# Soprano2GX-015.net
KiCad netlist of a schematic drawn in EAGLE
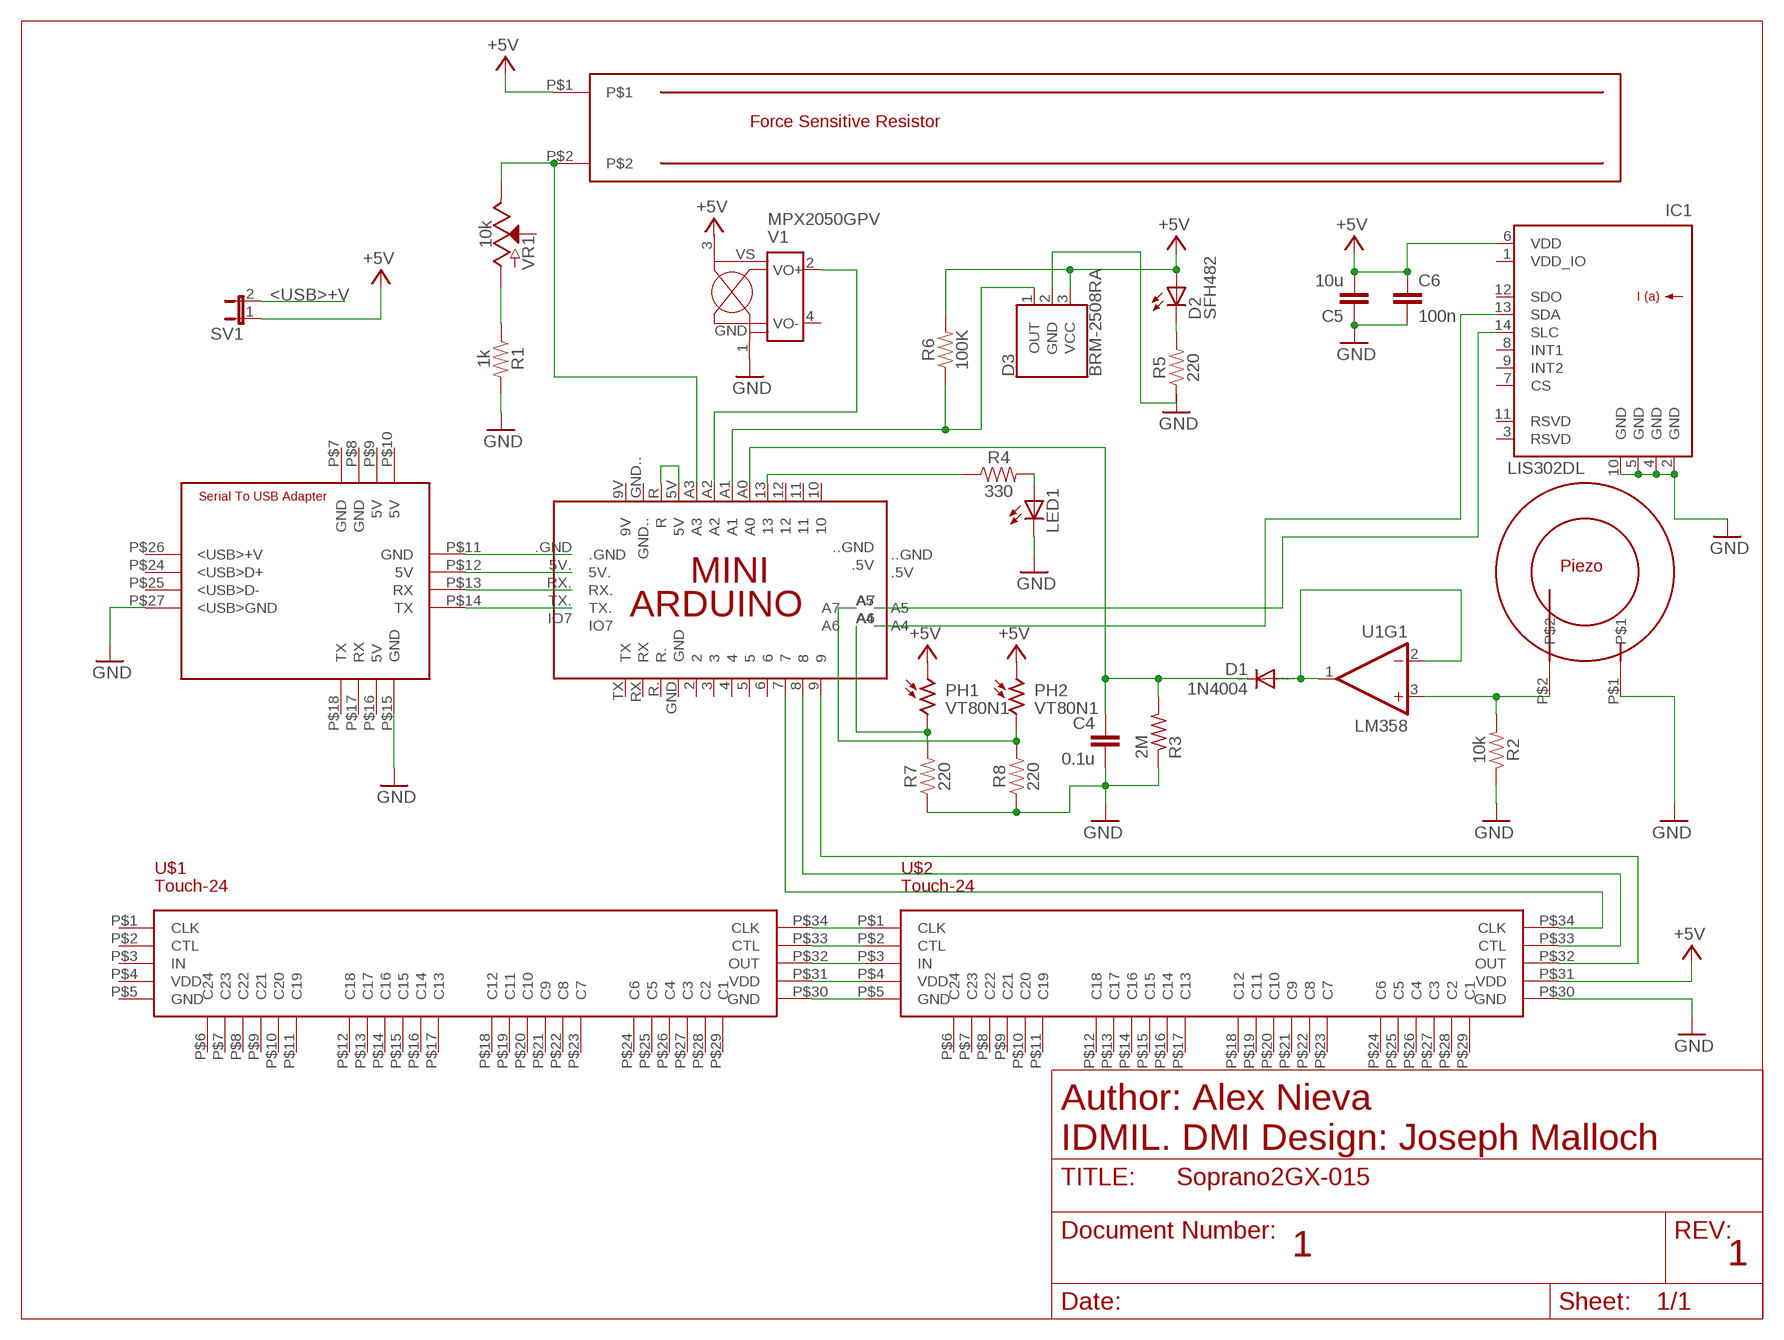
[diagram p0: schematic, sheet 1]

(export (version "E")
  (design (tool "Eeschema 10.0.6"))
  (components
    (comp (ref "C4")
      (value "0.1u")
      (footprint "eagle-import:C5B5.5")
      (libsource (lib "eagle-import") (part "C5/5.5"))
    )
    (comp (ref "C5")
      (value "10u")
      (footprint "eagle-import:C5B5.5")
      (libsource (lib "eagle-import") (part "C5/5.5"))
    )
    (comp (ref "C6")
      (value "100n")
      (footprint "eagle-import:C5B5.5")
      (libsource (lib "eagle-import") (part "C5/5.5"))
    )
    (comp (ref "D1")
      (value "1N4004")
      (footprint "eagle-import:DO41-10")
      (libsource (lib "eagle-import") (part "1N4004"))
    )
    (comp (ref "D2")
      (value "SFH482")
      (footprint "eagle-import:SFH482")
      (libsource (lib "eagle-import") (part "SFH482"))
    )
    (comp (ref "D3")
      (value "BRM-2508RA")
      (footprint "eagle-import:BRM-2508")
      (libsource (lib "eagle-import") (part "BRM-2508RA"))
    )
    (comp (ref "IC1")
      (value "LIS302DL")
      (footprint "eagle-import:LGA-14")
      (libsource (lib "eagle-import") (part "LIS302DL"))
    )
    (comp (ref "LED1")
      (value "LED3MM")
      (footprint "eagle-import:LED3MM")
      (libsource (lib "eagle-import") (part "LED3MM"))
    )
    (comp (ref "PCB1")
      (value "ARDUINO_MINI")
      (footprint "eagle-import:ARDUINO_MINI")
      (libsource (lib "eagle-import") (part "ARDUINO_MINI"))
    )
    (comp (ref "PH1")
      (value "VT80N1")
      (footprint "eagle-import:VT800")
      (libsource (lib "eagle-import") (part "VT80N1"))
    )
    (comp (ref "PH2")
      (value "VT80N1")
      (footprint "eagle-import:VT800")
      (libsource (lib "eagle-import") (part "VT80N1"))
    )
    (comp (ref "R1")
      (value "1k")
      (footprint "eagle-import:AXIAL-0.3")
      (libsource (lib "eagle-import") (part "1KOHM-HORIZ-1/4W-1%"))
    )
    (comp (ref "R2")
      (value "10k")
      (footprint "eagle-import:AXIAL-0.3")
      (libsource (lib "eagle-import") (part "10KOHM-HORIZ-1/4W-1%"))
    )
    (comp (ref "R3")
      (value "2M")
      (footprint "eagle-import:0204_7")
      (libsource (lib "eagle-import") (part "R-US_0204/7"))
    )
    (comp (ref "R4")
      (value "330")
      (footprint "eagle-import:AXIAL-0.3")
      (libsource (lib "eagle-import") (part "1KOHM-HORIZ-1/4W-1%"))
    )
    (comp (ref "R5")
      (value "220")
      (footprint "eagle-import:AXIAL-0.3")
      (libsource (lib "eagle-import") (part "1KOHM-HORIZ-1/4W-1%"))
    )
    (comp (ref "R6")
      (value "100K")
      (footprint "eagle-import:AXIAL-0.3")
      (libsource (lib "eagle-import") (part "1KOHM-HORIZ-1/4W-1%"))
    )
    (comp (ref "R7")
      (value "220")
      (footprint "eagle-import:AXIAL-0.3")
      (libsource (lib "eagle-import") (part "1KOHM-HORIZ-1/4W-1%"))
    )
    (comp (ref "R8")
      (value "220")
      (footprint "eagle-import:AXIAL-0.3")
      (libsource (lib "eagle-import") (part "1KOHM-HORIZ-1/4W-1%"))
    )
    (comp (ref "SV1")
      (value "JP1E")
      (footprint "eagle-import:JP1")
      (libsource (lib "eagle-import") (part "JP1E"))
    )
    (comp (ref "U$1")
      (value "TOUCH-24TOUCH-24")
      (footprint "eagle-import:TOUCH24")
      (libsource (lib "eagle-import") (part "TOUCH-24TOUCH-24"))
    )
    (comp (ref "U$2")
      (value "TOUCH-24TOUCH-24")
      (footprint "eagle-import:TOUCH24")
      (libsource (lib "eagle-import") (part "TOUCH-24TOUCH-24"))
    )
    (comp (ref "U$4")
      (value "SERIAL_TO_USB_ARDUINO_MINI")
      (footprint "eagle-import:SERIAL_TO_USB_ARDUINO")
      (libsource (lib "eagle-import") (part "SERIAL_TO_USB_ARDUINO_MINI"))
    )
    (comp (ref "U$5")
      (value "FSR_T-STICK")
      (footprint "eagle-import:FSR_T-STICK")
      (libsource (lib "eagle-import") (part "FSR_T-STICK"))
    )
    (comp (ref "U$6")
      (value "PIEZO_TSTICK")
      (footprint "eagle-import:PIEZO_TSTICK")
      (libsource (lib "eagle-import") (part "PIEZO_TSTICK"))
    )
    (comp (ref "U1")
      (value "LM358")
      (footprint "eagle-import:DIP08")
      (libsource (lib "eagle-import") (part "LM358"))
    )
    (comp (ref "V1")
      (value "MPX2050GPV")
      (footprint "eagle-import:MPX2050GPV")
      (fields (field (name "MF") "MOTOROLA") (field (name "MPN") "MPX2050GP"))
      (libsource (lib "eagle-import") (part "MPX2050GPV"))
    )
    (comp (ref "VR1")
      (value "10k")
      (footprint "eagle-import:POT-PTH-ALPS")
      (libsource (lib "eagle-import") (part "POTENTIOMETER-PTH-9MM-1/20W-20%"))
    )
  )
  (nets
    (net (code "1") (name "+5V") (class "Default")
      (node (ref "C5") (pin "2") (pinfunction "2_2") (pintype "passive"))
      (node (ref "C6") (pin "1") (pinfunction "1_1") (pintype "passive"))
      (node (ref "D2") (pin "A") (pinfunction "A_A") (pintype "passive"))
      (node (ref "D3") (pin "3") (pinfunction "VCC_3") (pintype "bidirectional"))
      (node (ref "IC1") (pin "6") (pinfunction "VDD_6") (pintype "power_in"))
      (node (ref "PCB1") (pin "5V.") (pinfunction "5V._5V.") (pintype "bidirectional"))
      (node (ref "R6") (pin "P$2") (pinfunction "2_P$2") (pintype "passive"))
      (node (ref "SV1") (pin "1") (pinfunction "1_1") (pintype "passive"))
      (node (ref "U$2") (pin "P$31") (pinfunction "VDD_P$31") (pintype "bidirectional"))
      (node (ref "U$4") (pin "P$12") (pinfunction "5V_P$12") (pintype "bidirectional"))
      (node (ref "U$5") (pin "P$1") (pinfunction "P$1_P$1") (pintype "bidirectional"))
    )
    (net (code "2") (name "/<USB>+V") (class "Default")
      (node (ref "SV1") (pin "2") (pinfunction "2_2") (pintype "passive"))
    )
    (net (code "3") (name "/VDD_IO") (class "Default")
      (node (ref "IC1") (pin "1") (pinfunction "VDD_IO_1") (pintype "power_in"))
    )
    (net (code "4") (name "GND") (class "Default")
      (node (ref "C4") (pin "2") (pinfunction "2_2") (pintype "passive"))
      (node (ref "C5") (pin "1") (pinfunction "1_1") (pintype "passive"))
      (node (ref "C6") (pin "2") (pinfunction "2_2") (pintype "passive"))
      (node (ref "IC1") (pin "10") (pinfunction "GND_10") (pintype "passive"))
      (node (ref "IC1") (pin "2") (pinfunction "GND_2") (pintype "power_in"))
      (node (ref "IC1") (pin "4") (pinfunction "GND_4") (pintype "passive"))
      (node (ref "IC1") (pin "5") (pinfunction "GND_5") (pintype "passive"))
      (node (ref "LED1") (pin "K") (pinfunction "C_K") (pintype "passive"))
      (node (ref "R1") (pin "P$2") (pinfunction "2_P$2") (pintype "passive"))
      (node (ref "R2") (pin "P$1") (pinfunction "1_P$1") (pintype "passive"))
      (node (ref "R3") (pin "1") (pinfunction "1_1") (pintype "passive"))
      (node (ref "R7") (pin "P$1") (pinfunction "1_P$1") (pintype "passive"))
      (node (ref "R8") (pin "P$1") (pinfunction "1_P$1") (pintype "passive"))
      (node (ref "U$2") (pin "P$30") (pinfunction "GND_P$30") (pintype "bidirectional"))
      (node (ref "U$4") (pin "P$15") (pinfunction "GND_P$15") (pintype "bidirectional"))
      (node (ref "U$4") (pin "P$27") (pinfunction "<USB>GND_P$27") (pintype "bidirectional"))
      (node (ref "U$6") (pin "P$1") (pinfunction "P$1_P$1") (pintype "bidirectional"))
      (node (ref "V1") (pin "1") (pinfunction "GND_1") (pintype "passive"))
    )
    (net (code "5") (name "Net-(C4-Pad1)") (class "Default")
      (node (ref "C4") (pin "1") (pinfunction "1_1") (pintype "passive"))
      (node (ref "D1") (pin "C") (pinfunction "C_C") (pintype "passive"))
      (node (ref "PCB1") (pin "A0") (pinfunction "A0_A0") (pintype "bidirectional"))
      (node (ref "R3") (pin "2") (pinfunction "2_2") (pintype "passive"))
    )
    (net (code "6") (name "Net-(D2-C)") (class "Default")
      (node (ref "D2") (pin "K") (pinfunction "C_K") (pintype "passive"))
      (node (ref "R5") (pin "P$2") (pinfunction "2_P$2") (pintype "passive"))
    )
    (net (code "7") (name "Net-(D3-GND)") (class "Default")
      (node (ref "D3") (pin "2") (pinfunction "GND_2") (pintype "bidirectional"))
      (node (ref "R5") (pin "P$1") (pinfunction "1_P$1") (pintype "passive"))
    )
    (net (code "8") (name "Net-(D3-OUT)") (class "Default")
      (node (ref "D3") (pin "1") (pinfunction "OUT_1") (pintype "bidirectional"))
      (node (ref "PCB1") (pin "A1") (pinfunction "A1_A1") (pintype "bidirectional"))
      (node (ref "R6") (pin "P$1") (pinfunction "1_P$1") (pintype "passive"))
    )
    (net (code "9") (name "Net-(IC1-SDA)") (class "Default")
      (node (ref "IC1") (pin "13") (pinfunction "SDA_13") (pintype "bidirectional"))
      (node (ref "PCB1") (pin "A4") (pinfunction "A4_A4") (pintype "bidirectional"))
    )
    (net (code "10") (name "Net-(IC1-SLC)") (class "Default")
      (node (ref "IC1") (pin "14") (pinfunction "SLC_14") (pintype "bidirectional"))
      (node (ref "PCB1") (pin "A5") (pinfunction "A5_A5") (pintype "bidirectional"))
    )
    (net (code "11") (name "Net-(PCB1-Pad.GND)") (class "Default")
      (node (ref "PCB1") (pin ".GND") (pinfunction ".GND_.GND") (pintype "bidirectional"))
      (node (ref "U$4") (pin "P$11") (pinfunction "GND_P$11") (pintype "bidirectional"))
    )
    (net (code "12") (name "Net-(PCB1-Pad5V)") (class "Default")
      (node (ref "PCB1") (pin "5V") (pinfunction "5V_5V") (pintype "bidirectional"))
      (node (ref "PCB1") (pin "R") (pinfunction "R_R") (pintype "bidirectional"))
    )
    (net (code "13") (name "Net-(PCB1-Pad7)") (class "Default")
      (node (ref "PCB1") (pin "7") (pinfunction "7_7") (pintype "bidirectional"))
      (node (ref "U$2") (pin "P$34") (pinfunction "CLK_P$34") (pintype "bidirectional"))
    )
    (net (code "14") (name "Net-(PCB1-Pad8)") (class "Default")
      (node (ref "PCB1") (pin "8") (pinfunction "8_8") (pintype "bidirectional"))
      (node (ref "U$2") (pin "P$33") (pinfunction "CTL_P$33") (pintype "bidirectional"))
    )
    (net (code "15") (name "Net-(PCB1-PadRX.)") (class "Default")
      (node (ref "PCB1") (pin "RX.") (pinfunction "RX._RX.") (pintype "bidirectional"))
      (node (ref "U$4") (pin "P$13") (pinfunction "RX_P$13") (pintype "bidirectional"))
    )
    (net (code "16") (name "Net-(PCB1-PadTX.)") (class "Default")
      (node (ref "PCB1") (pin "TX.") (pinfunction "TX._TX.") (pintype "bidirectional"))
      (node (ref "U$4") (pin "P$14") (pinfunction "TX_P$14") (pintype "bidirectional"))
    )
    (net (code "17") (name "Net-(R1-1)") (class "Default")
      (node (ref "R1") (pin "P$1") (pinfunction "1_P$1") (pintype "passive"))
      (node (ref "VR1") (pin "P$3") (pinfunction "A_P$3") (pintype "passive"))
    )
    (net (code "18") (name "Net-(R2-2)") (class "Default")
      (node (ref "R2") (pin "P$2") (pinfunction "2_P$2") (pintype "passive"))
      (node (ref "U$6") (pin "P$2") (pinfunction "P$2_P$2") (pintype "bidirectional"))
      (node (ref "U1") (pin "3") (pinfunction "+IN_3") (pintype "input"))
    )
    (net (code "19") (name "Net-(R4-1)") (class "Default")
      (node (ref "PCB1") (pin "13") (pinfunction "13_13") (pintype "bidirectional"))
      (node (ref "R4") (pin "P$1") (pinfunction "1_P$1") (pintype "passive"))
    )
    (net (code "20") (name "Net-(R4-2)") (class "Default")
      (node (ref "LED1") (pin "A") (pinfunction "A_A") (pintype "passive"))
      (node (ref "R4") (pin "P$2") (pinfunction "2_P$2") (pintype "passive"))
    )
    (net (code "21") (name "Net-(R7-2)") (class "Default")
      (node (ref "PCB1") (pin "A6") (pinfunction "A6_A6") (pintype "bidirectional"))
      (node (ref "PH1") (pin "2") (pinfunction "2_2") (pintype "passive"))
      (node (ref "R7") (pin "P$2") (pinfunction "2_P$2") (pintype "passive"))
    )
    (net (code "22") (name "Net-(R8-2)") (class "Default")
      (node (ref "PCB1") (pin "A7") (pinfunction "A7_A7") (pintype "bidirectional"))
      (node (ref "PH2") (pin "2") (pinfunction "2_2") (pintype "passive"))
      (node (ref "R8") (pin "P$2") (pinfunction "2_P$2") (pintype "passive"))
    )
    (net (code "23") (name "Net-(U$1-CLK-PadP$34)") (class "Default")
      (node (ref "U$1") (pin "P$34") (pinfunction "CLK_P$34") (pintype "bidirectional"))
      (node (ref "U$2") (pin "P$1") (pinfunction "CLK_P$1") (pintype "bidirectional"))
    )
    (net (code "24") (name "Net-(U$1-CTL-PadP$33)") (class "Default")
      (node (ref "U$1") (pin "P$33") (pinfunction "CTL_P$33") (pintype "bidirectional"))
      (node (ref "U$2") (pin "P$2") (pinfunction "CTL_P$2") (pintype "bidirectional"))
    )
    (net (code "25") (name "Net-(U$1-GND-PadP$30)") (class "Default")
      (node (ref "U$1") (pin "P$30") (pinfunction "GND_P$30") (pintype "bidirectional"))
      (node (ref "U$2") (pin "P$5") (pinfunction "GND_P$5") (pintype "bidirectional"))
    )
    (net (code "26") (name "Net-(U$1-OUT)") (class "Default")
      (node (ref "U$1") (pin "P$32") (pinfunction "OUT_P$32") (pintype "bidirectional"))
      (node (ref "U$2") (pin "P$3") (pinfunction "IN_P$3") (pintype "bidirectional"))
    )
    (net (code "27") (name "Net-(U$1-VDD-PadP$31)") (class "Default")
      (node (ref "U$1") (pin "P$31") (pinfunction "VDD_P$31") (pintype "bidirectional"))
      (node (ref "U$2") (pin "P$4") (pinfunction "VDD_P$4") (pintype "bidirectional"))
    )
    (net (code "28") (name "Net-(U$2-OUT)") (class "Default")
      (node (ref "PCB1") (pin "9") (pinfunction "9_9") (pintype "bidirectional"))
      (node (ref "U$2") (pin "P$32") (pinfunction "OUT_P$32") (pintype "bidirectional"))
    )
    (net (code "29") (name "Net-(U1A--IN)") (class "Default")
      (node (ref "D1") (pin "A") (pinfunction "A_A") (pintype "passive"))
      (node (ref "U1") (pin "1") (pinfunction "OUT_1") (pintype "output"))
      (node (ref "U1") (pin "2") (pinfunction "-IN_2") (pintype "input"))
    )
    (net (code "30") (name "Net-(V1-VO+)") (class "Default")
      (node (ref "PCB1") (pin "A2") (pinfunction "A2_A2") (pintype "bidirectional"))
      (node (ref "V1") (pin "2") (pinfunction "VO+_2") (pintype "passive"))
    )
    (net (code "31") (name "Net-(VR1-E)") (class "Default")
      (node (ref "PCB1") (pin "A3") (pinfunction "A3_A3") (pintype "bidirectional"))
      (node (ref "U$5") (pin "P$2") (pinfunction "P$2_P$2") (pintype "bidirectional"))
      (node (ref "VR1") (pin "P$1") (pinfunction "E_P$1") (pintype "passive"))
    )
    (net (code "32") (name "unconnected-(IC1-CS-Pad7)") (class "Default")
      (node (ref "IC1") (pin "7") (pinfunction "CS_7") (pintype "bidirectional"))
    )
    (net (code "33") (name "unconnected-(IC1-INT1-Pad8)") (class "Default")
      (node (ref "IC1") (pin "8") (pinfunction "INT1_8") (pintype "bidirectional"))
    )
    (net (code "34") (name "unconnected-(IC1-INT2-Pad9)") (class "Default")
      (node (ref "IC1") (pin "9") (pinfunction "INT2_9") (pintype "bidirectional"))
    )
    (net (code "35") (name "unconnected-(IC1-RSVD-Pad3)") (class "Default")
      (node (ref "IC1") (pin "3") (pinfunction "RSVD_3") (pintype "passive"))
    )
    (net (code "36") (name "unconnected-(IC1-RSVD-Pad11)") (class "Default")
      (node (ref "IC1") (pin "11") (pinfunction "RSVD_11") (pintype "passive"))
    )
    (net (code "37") (name "unconnected-(IC1-SDO-Pad12)") (class "Default")
      (node (ref "IC1") (pin "12") (pinfunction "SDO_12") (pintype "bidirectional"))
    )
    (net (code "38") (name "unconnected-(PCB1-Pad..GND)") (class "Default")
      (node (ref "PCB1") (pin "..GND") (pinfunction "..GND_..GND") (pintype "bidirectional"))
    )
    (net (code "39") (name "unconnected-(PCB1-Pad.5V)") (class "Default")
      (node (ref "PCB1") (pin ".5V") (pinfunction ".5V_.5V") (pintype "bidirectional"))
    )
    (net (code "40") (name "unconnected-(PCB1-Pad2)") (class "Default")
      (node (ref "PCB1") (pin "2") (pinfunction "2_2") (pintype "bidirectional"))
    )
    (net (code "41") (name "unconnected-(PCB1-Pad3)") (class "Default")
      (node (ref "PCB1") (pin "3") (pinfunction "3_3") (pintype "bidirectional"))
    )
    (net (code "42") (name "unconnected-(PCB1-Pad4)") (class "Default")
      (node (ref "PCB1") (pin "4") (pinfunction "4_4") (pintype "bidirectional"))
    )
    (net (code "43") (name "unconnected-(PCB1-Pad5)") (class "Default")
      (node (ref "PCB1") (pin "5") (pinfunction "5_5") (pintype "bidirectional"))
    )
    (net (code "44") (name "unconnected-(PCB1-Pad6)") (class "Default")
      (node (ref "PCB1") (pin "6") (pinfunction "6_6") (pintype "bidirectional"))
    )
    (net (code "45") (name "unconnected-(PCB1-Pad9V)") (class "Default")
      (node (ref "PCB1") (pin "9V") (pinfunction "9V_9V") (pintype "bidirectional"))
    )
    (net (code "46") (name "unconnected-(PCB1-Pad10)") (class "Default")
      (node (ref "PCB1") (pin "10") (pinfunction "10_10") (pintype "bidirectional"))
    )
    (net (code "47") (name "unconnected-(PCB1-Pad11)") (class "Default")
      (node (ref "PCB1") (pin "11") (pinfunction "11_11") (pintype "bidirectional"))
    )
    (net (code "48") (name "unconnected-(PCB1-Pad12)") (class "Default")
      (node (ref "PCB1") (pin "12") (pinfunction "12_12") (pintype "bidirectional"))
    )
    (net (code "49") (name "unconnected-(PCB1-PadGND)") (class "Default")
      (node (ref "PCB1") (pin "GND") (pinfunction "GND_GND") (pintype "bidirectional"))
    )
    (net (code "50") (name "unconnected-(PCB1-PadGND..)") (class "Default")
      (node (ref "PCB1") (pin "GND..") (pinfunction "GND.._GND..") (pintype "bidirectional"))
    )
    (net (code "51") (name "unconnected-(PCB1-PadIO7)") (class "Default")
      (node (ref "PCB1") (pin "IO7") (pinfunction "IO7_IO7") (pintype "bidirectional"))
    )
    (net (code "52") (name "unconnected-(PCB1-PadR.)") (class "Default")
      (node (ref "PCB1") (pin "R.") (pinfunction "R._R.") (pintype "bidirectional"))
    )
    (net (code "53") (name "unconnected-(PCB1-PadRX)") (class "Default")
      (node (ref "PCB1") (pin "RX") (pinfunction "RX_RX") (pintype "bidirectional"))
    )
    (net (code "54") (name "unconnected-(PCB1-PadTX)") (class "Default")
      (node (ref "PCB1") (pin "TX") (pinfunction "TX_TX") (pintype "bidirectional"))
    )
    (net (code "55") (name "unconnected-(PH1-Pad1)") (class "Default")
      (node (ref "PH1") (pin "1") (pinfunction "1_1") (pintype "passive"))
    )
    (net (code "56") (name "unconnected-(PH2-Pad1)") (class "Default")
      (node (ref "PH2") (pin "1") (pinfunction "1_1") (pintype "passive"))
    )
    (net (code "57") (name "unconnected-(U$1-C1-PadP$29)") (class "Default")
      (node (ref "U$1") (pin "P$29") (pinfunction "C1_P$29") (pintype "bidirectional"))
    )
    (net (code "58") (name "unconnected-(U$1-C2-PadP$28)") (class "Default")
      (node (ref "U$1") (pin "P$28") (pinfunction "C2_P$28") (pintype "bidirectional"))
    )
    (net (code "59") (name "unconnected-(U$1-C3-PadP$27)") (class "Default")
      (node (ref "U$1") (pin "P$27") (pinfunction "C3_P$27") (pintype "bidirectional"))
    )
    (net (code "60") (name "unconnected-(U$1-C4-PadP$26)") (class "Default")
      (node (ref "U$1") (pin "P$26") (pinfunction "C4_P$26") (pintype "bidirectional"))
    )
    (net (code "61") (name "unconnected-(U$1-C5-PadP$25)") (class "Default")
      (node (ref "U$1") (pin "P$25") (pinfunction "C5_P$25") (pintype "bidirectional"))
    )
    (net (code "62") (name "unconnected-(U$1-C6-PadP$24)") (class "Default")
      (node (ref "U$1") (pin "P$24") (pinfunction "C6_P$24") (pintype "bidirectional"))
    )
    (net (code "63") (name "unconnected-(U$1-C7-PadP$23)") (class "Default")
      (node (ref "U$1") (pin "P$23") (pinfunction "C7_P$23") (pintype "bidirectional"))
    )
    (net (code "64") (name "unconnected-(U$1-C8-PadP$22)") (class "Default")
      (node (ref "U$1") (pin "P$22") (pinfunction "C8_P$22") (pintype "bidirectional"))
    )
    (net (code "65") (name "unconnected-(U$1-C9-PadP$21)") (class "Default")
      (node (ref "U$1") (pin "P$21") (pinfunction "C9_P$21") (pintype "bidirectional"))
    )
    (net (code "66") (name "unconnected-(U$1-C10-PadP$20)") (class "Default")
      (node (ref "U$1") (pin "P$20") (pinfunction "C10_P$20") (pintype "bidirectional"))
    )
    (net (code "67") (name "unconnected-(U$1-C11-PadP$19)") (class "Default")
      (node (ref "U$1") (pin "P$19") (pinfunction "C11_P$19") (pintype "bidirectional"))
    )
    (net (code "68") (name "unconnected-(U$1-C12-PadP$18)") (class "Default")
      (node (ref "U$1") (pin "P$18") (pinfunction "C12_P$18") (pintype "bidirectional"))
    )
    (net (code "69") (name "unconnected-(U$1-C13-PadP$17)") (class "Default")
      (node (ref "U$1") (pin "P$17") (pinfunction "C13_P$17") (pintype "bidirectional"))
    )
    (net (code "70") (name "unconnected-(U$1-C14-PadP$16)") (class "Default")
      (node (ref "U$1") (pin "P$16") (pinfunction "C14_P$16") (pintype "bidirectional"))
    )
    (net (code "71") (name "unconnected-(U$1-C15-PadP$15)") (class "Default")
      (node (ref "U$1") (pin "P$15") (pinfunction "C15_P$15") (pintype "bidirectional"))
    )
    (net (code "72") (name "unconnected-(U$1-C16-PadP$14)") (class "Default")
      (node (ref "U$1") (pin "P$14") (pinfunction "C16_P$14") (pintype "bidirectional"))
    )
    (net (code "73") (name "unconnected-(U$1-C17-PadP$13)") (class "Default")
      (node (ref "U$1") (pin "P$13") (pinfunction "C17_P$13") (pintype "bidirectional"))
    )
    (net (code "74") (name "unconnected-(U$1-C18-PadP$12)") (class "Default")
      (node (ref "U$1") (pin "P$12") (pinfunction "C18_P$12") (pintype "bidirectional"))
    )
    (net (code "75") (name "unconnected-(U$1-C19-PadP$11)") (class "Default")
      (node (ref "U$1") (pin "P$11") (pinfunction "C19_P$11") (pintype "bidirectional"))
    )
    (net (code "76") (name "unconnected-(U$1-C20-PadP$10)") (class "Default")
      (node (ref "U$1") (pin "P$10") (pinfunction "C20_P$10") (pintype "bidirectional"))
    )
    (net (code "77") (name "unconnected-(U$1-C21-PadP$9)") (class "Default")
      (node (ref "U$1") (pin "P$9") (pinfunction "C21_P$9") (pintype "bidirectional"))
    )
    (net (code "78") (name "unconnected-(U$1-C22-PadP$8)") (class "Default")
      (node (ref "U$1") (pin "P$8") (pinfunction "C22_P$8") (pintype "bidirectional"))
    )
    (net (code "79") (name "unconnected-(U$1-C23-PadP$7)") (class "Default")
      (node (ref "U$1") (pin "P$7") (pinfunction "C23_P$7") (pintype "bidirectional"))
    )
    (net (code "80") (name "unconnected-(U$1-C24-PadP$6)") (class "Default")
      (node (ref "U$1") (pin "P$6") (pinfunction "C24_P$6") (pintype "bidirectional"))
    )
    (net (code "81") (name "unconnected-(U$1-CLK-PadP$1)") (class "Default")
      (node (ref "U$1") (pin "P$1") (pinfunction "CLK_P$1") (pintype "bidirectional"))
    )
    (net (code "82") (name "unconnected-(U$1-CTL-PadP$2)") (class "Default")
      (node (ref "U$1") (pin "P$2") (pinfunction "CTL_P$2") (pintype "bidirectional"))
    )
    (net (code "83") (name "unconnected-(U$1-GND-PadP$5)") (class "Default")
      (node (ref "U$1") (pin "P$5") (pinfunction "GND_P$5") (pintype "bidirectional"))
    )
    (net (code "84") (name "unconnected-(U$1-IN-PadP$3)") (class "Default")
      (node (ref "U$1") (pin "P$3") (pinfunction "IN_P$3") (pintype "bidirectional"))
    )
    (net (code "85") (name "unconnected-(U$1-VDD-PadP$4)") (class "Default")
      (node (ref "U$1") (pin "P$4") (pinfunction "VDD_P$4") (pintype "bidirectional"))
    )
    (net (code "86") (name "unconnected-(U$2-C1-PadP$29)") (class "Default")
      (node (ref "U$2") (pin "P$29") (pinfunction "C1_P$29") (pintype "bidirectional"))
    )
    (net (code "87") (name "unconnected-(U$2-C2-PadP$28)") (class "Default")
      (node (ref "U$2") (pin "P$28") (pinfunction "C2_P$28") (pintype "bidirectional"))
    )
    (net (code "88") (name "unconnected-(U$2-C3-PadP$27)") (class "Default")
      (node (ref "U$2") (pin "P$27") (pinfunction "C3_P$27") (pintype "bidirectional"))
    )
    (net (code "89") (name "unconnected-(U$2-C4-PadP$26)") (class "Default")
      (node (ref "U$2") (pin "P$26") (pinfunction "C4_P$26") (pintype "bidirectional"))
    )
    (net (code "90") (name "unconnected-(U$2-C5-PadP$25)") (class "Default")
      (node (ref "U$2") (pin "P$25") (pinfunction "C5_P$25") (pintype "bidirectional"))
    )
    (net (code "91") (name "unconnected-(U$2-C6-PadP$24)") (class "Default")
      (node (ref "U$2") (pin "P$24") (pinfunction "C6_P$24") (pintype "bidirectional"))
    )
    (net (code "92") (name "unconnected-(U$2-C7-PadP$23)") (class "Default")
      (node (ref "U$2") (pin "P$23") (pinfunction "C7_P$23") (pintype "bidirectional"))
    )
    (net (code "93") (name "unconnected-(U$2-C8-PadP$22)") (class "Default")
      (node (ref "U$2") (pin "P$22") (pinfunction "C8_P$22") (pintype "bidirectional"))
    )
    (net (code "94") (name "unconnected-(U$2-C9-PadP$21)") (class "Default")
      (node (ref "U$2") (pin "P$21") (pinfunction "C9_P$21") (pintype "bidirectional"))
    )
    (net (code "95") (name "unconnected-(U$2-C10-PadP$20)") (class "Default")
      (node (ref "U$2") (pin "P$20") (pinfunction "C10_P$20") (pintype "bidirectional"))
    )
    (net (code "96") (name "unconnected-(U$2-C11-PadP$19)") (class "Default")
      (node (ref "U$2") (pin "P$19") (pinfunction "C11_P$19") (pintype "bidirectional"))
    )
    (net (code "97") (name "unconnected-(U$2-C12-PadP$18)") (class "Default")
      (node (ref "U$2") (pin "P$18") (pinfunction "C12_P$18") (pintype "bidirectional"))
    )
    (net (code "98") (name "unconnected-(U$2-C13-PadP$17)") (class "Default")
      (node (ref "U$2") (pin "P$17") (pinfunction "C13_P$17") (pintype "bidirectional"))
    )
    (net (code "99") (name "unconnected-(U$2-C14-PadP$16)") (class "Default")
      (node (ref "U$2") (pin "P$16") (pinfunction "C14_P$16") (pintype "bidirectional"))
    )
    (net (code "100") (name "unconnected-(U$2-C15-PadP$15)") (class "Default")
      (node (ref "U$2") (pin "P$15") (pinfunction "C15_P$15") (pintype "bidirectional"))
    )
    (net (code "101") (name "unconnected-(U$2-C16-PadP$14)") (class "Default")
      (node (ref "U$2") (pin "P$14") (pinfunction "C16_P$14") (pintype "bidirectional"))
    )
    (net (code "102") (name "unconnected-(U$2-C17-PadP$13)") (class "Default")
      (node (ref "U$2") (pin "P$13") (pinfunction "C17_P$13") (pintype "bidirectional"))
    )
    (net (code "103") (name "unconnected-(U$2-C18-PadP$12)") (class "Default")
      (node (ref "U$2") (pin "P$12") (pinfunction "C18_P$12") (pintype "bidirectional"))
    )
    (net (code "104") (name "unconnected-(U$2-C19-PadP$11)") (class "Default")
      (node (ref "U$2") (pin "P$11") (pinfunction "C19_P$11") (pintype "bidirectional"))
    )
    (net (code "105") (name "unconnected-(U$2-C20-PadP$10)") (class "Default")
      (node (ref "U$2") (pin "P$10") (pinfunction "C20_P$10") (pintype "bidirectional"))
    )
    (net (code "106") (name "unconnected-(U$2-C21-PadP$9)") (class "Default")
      (node (ref "U$2") (pin "P$9") (pinfunction "C21_P$9") (pintype "bidirectional"))
    )
    (net (code "107") (name "unconnected-(U$2-C22-PadP$8)") (class "Default")
      (node (ref "U$2") (pin "P$8") (pinfunction "C22_P$8") (pintype "bidirectional"))
    )
    (net (code "108") (name "unconnected-(U$2-C23-PadP$7)") (class "Default")
      (node (ref "U$2") (pin "P$7") (pinfunction "C23_P$7") (pintype "bidirectional"))
    )
    (net (code "109") (name "unconnected-(U$2-C24-PadP$6)") (class "Default")
      (node (ref "U$2") (pin "P$6") (pinfunction "C24_P$6") (pintype "bidirectional"))
    )
    (net (code "110") (name "unconnected-(U$4-5V-PadP$9)") (class "Default")
      (node (ref "U$4") (pin "P$9") (pinfunction "5V_P$9") (pintype "bidirectional"))
    )
    (net (code "111") (name "unconnected-(U$4-5V-PadP$10)") (class "Default")
      (node (ref "U$4") (pin "P$10") (pinfunction "5V_P$10") (pintype "bidirectional"))
    )
    (net (code "112") (name "unconnected-(U$4-5V-PadP$16)") (class "Default")
      (node (ref "U$4") (pin "P$16") (pinfunction "5V_P$16") (pintype "bidirectional"))
    )
    (net (code "113") (name "unconnected-(U$4-<USB>+V-PadP$26)") (class "Default")
      (node (ref "U$4") (pin "P$26") (pinfunction "<USB>+V_P$26") (pintype "bidirectional"))
    )
    (net (code "114") (name "unconnected-(U$4-<USB>D+-PadP$24)") (class "Default")
      (node (ref "U$4") (pin "P$24") (pinfunction "<USB>D+_P$24") (pintype "bidirectional"))
    )
    (net (code "115") (name "unconnected-(U$4-<USB>D--PadP$25)") (class "Default")
      (node (ref "U$4") (pin "P$25") (pinfunction "<USB>D-_P$25") (pintype "bidirectional"))
    )
    (net (code "116") (name "unconnected-(U$4-GND-PadP$7)") (class "Default")
      (node (ref "U$4") (pin "P$7") (pinfunction "GND_P$7") (pintype "bidirectional"))
    )
    (net (code "117") (name "unconnected-(U$4-GND-PadP$8)") (class "Default")
      (node (ref "U$4") (pin "P$8") (pinfunction "GND_P$8") (pintype "bidirectional"))
    )
    (net (code "118") (name "unconnected-(U$4-RX-PadP$17)") (class "Default")
      (node (ref "U$4") (pin "P$17") (pinfunction "RX_P$17") (pintype "bidirectional"))
    )
    (net (code "119") (name "unconnected-(U$4-TX-PadP$18)") (class "Default")
      (node (ref "U$4") (pin "P$18") (pinfunction "TX_P$18") (pintype "bidirectional"))
    )
    (net (code "120") (name "unconnected-(V1-VO--Pad4)") (class "Default")
      (node (ref "V1") (pin "4") (pinfunction "VO-_4") (pintype "passive"))
    )
    (net (code "121") (name "unconnected-(V1-VS-Pad3)") (class "Default")
      (node (ref "V1") (pin "3") (pinfunction "VS_3") (pintype "passive"))
    )
    (net (code "122") (name "unconnected-(VR1-S-PadP$2)") (class "Default")
      (node (ref "VR1") (pin "P$2") (pinfunction "S_P$2") (pintype "passive"))
    )
  )
)
